# SCH_occitel_mini.net
KiCad netlist of a schematic drawn in EasyEDA
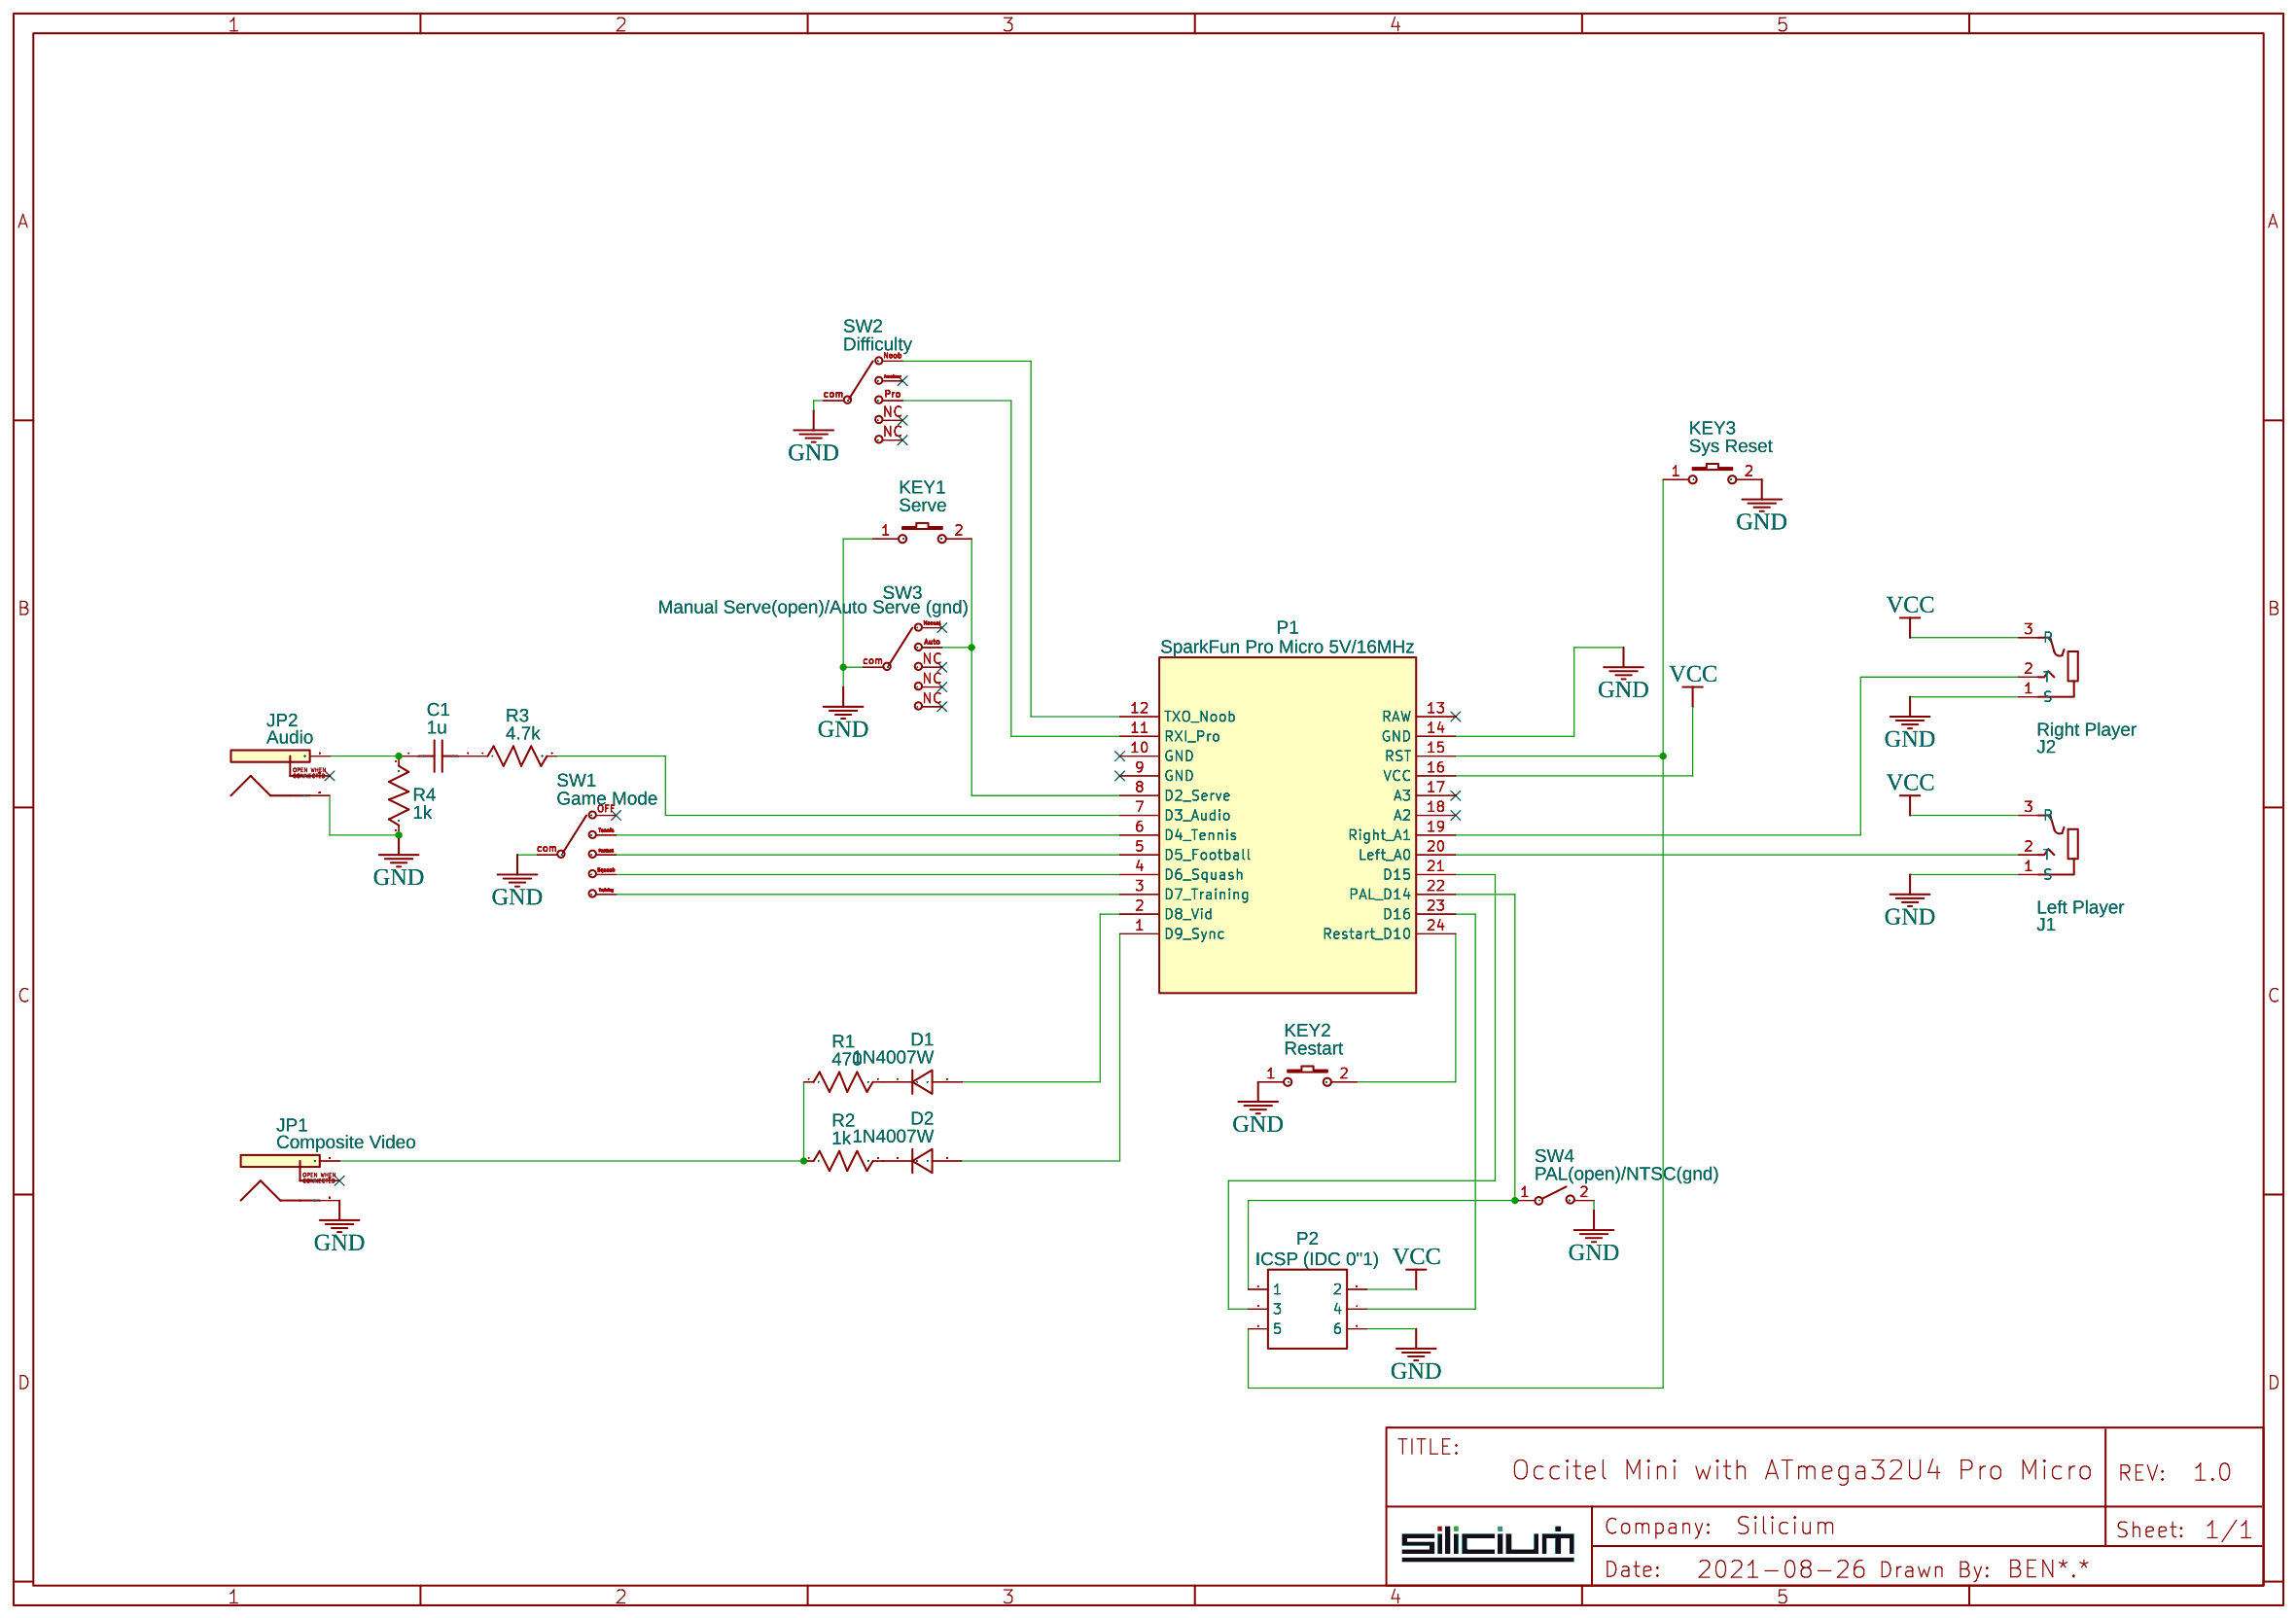
[diagram p0: schematic sheet]

(export (version "E")
  (design (tool "Eeschema 10.0.6"))
  (components
    (comp (ref "C1") (value "1u") (libsource (lib "") (part "C_0603_US")))
    (comp (ref "D1")
      (value "1N4007W")
      (fields (field (name "BOM_Supplier Part") "C328592"))
      (libsource (lib "") (part "1N4007W"))
    )
    (comp (ref "D2")
      (value "1N4007W")
      (fields (field (name "BOM_Supplier Part") "C328592"))
      (libsource (lib "") (part "1N4007W"))
    )
    (comp (ref "J1") (value "Left Player") (libsource (lib "") (part "Jack_3.5mm_3pin")))
    (comp (ref "J2") (value "Right Player") (libsource (lib "") (part "Jack_3.5mm_3pin")))
    (comp (ref "JP1") (value "Composite Video") (libsource (lib "") (part "RCA-LOCK")))
    (comp (ref "JP2") (value "Audio") (libsource (lib "") (part "RCA-LOCK")))
    (comp (ref "KEY1")
      (value "Serve")
      (fields
        (field (name "BOM_Manufacturer Part") "K2-1107ST-A4SW-06")
        (field (name "BOM_Supplier Part") "C118141")
      )
      (libsource (lib "") (part "K2-3.6×6.1_SMD"))
    )
    (comp (ref "KEY2")
      (value "Restart")
      (fields
        (field (name "BOM_Manufacturer Part") "K2-1107ST-A4SW-06")
        (field (name "BOM_Supplier Part") "C118141")
      )
      (libsource (lib "") (part "K2-3.6×6.1_SMD"))
    )
    (comp (ref "KEY3")
      (value "Sys Reset")
      (fields
        (field (name "BOM_Manufacturer Part") "K2-1107ST-A4SW-06")
        (field (name "BOM_Supplier Part") "C118141")
      )
      (libsource (lib "") (part "K2-3.6×6.1_SMD"))
    )
    (comp (ref "P1") (value "SparkFun Pro Micro 5V/16MHz") (libsource (lib "") (part "Pro Micro - 5V")))
    (comp (ref "P2")
      (value "ICSP (IDC 0\"1)")
      (fields
        (field (name "BOM_Manufacturer Part") "2X3 2.54mm IDC Box")
        (field (name "BOM_Supplier Part") "C11214")
      )
      (libsource (lib "") (part "HDR-IDC-2.54-2X3P"))
    )
    (comp (ref "R1") (value "470") (libsource (lib "") (part "R_0603_US")))
    (comp (ref "R2") (value "1k") (libsource (lib "") (part "R_0603_US")))
    (comp (ref "R3") (value "4.7k") (libsource (lib "") (part "R_0603_US")))
    (comp (ref "R4") (value "1k") (libsource (lib "") (part "R_0603_US_1")))
    (comp (ref "SW1") (value "Game Mode") (libsource (lib "") (part "SW_SP5T_2")))
    (comp (ref "SW2") (value "Difficulty") (libsource (lib "") (part "SW_SP5T_1")))
    (comp (ref "SW3") (value "Manual Serve(open)/Auto Serve (gnd)") (libsource (lib "") (part "SW_SP5T")))
    (comp (ref "SW4") (value "PAL(open)/NTSC(gnd)") (libsource (lib "") (part "SW_SPST")))
  )
  (nets
    (net (code "1") (name "GND") (class "Default")
      (node (ref "J1") (pin "1") (pinfunction "S_1") (pintype "unspecified"))
      (node (ref "J2") (pin "1") (pinfunction "S_1") (pintype "unspecified"))
      (node (ref "JP1") (pin "SHELL") (pinfunction "SHELL_SHELL") (pintype "unspecified"))
      (node (ref "JP2") (pin "SHELL") (pinfunction "SHELL_SHELL") (pintype "unspecified"))
      (node (ref "KEY1") (pin "1") (pinfunction "1_1") (pintype "unspecified"))
      (node (ref "KEY2") (pin "1") (pinfunction "1_1") (pintype "unspecified"))
      (node (ref "KEY3") (pin "2") (pinfunction "2_2") (pintype "unspecified"))
      (node (ref "P1") (pin "14") (pinfunction "GND_14") (pintype "unspecified"))
      (node (ref "P2") (pin "6") (pinfunction "6_6") (pintype "unspecified"))
      (node (ref "R4") (pin "1") (pinfunction "1_1") (pintype "unspecified"))
      (node (ref "SW1") (pin "com") (pinfunction "3_com") (pintype "unspecified"))
      (node (ref "SW2") (pin "com") (pinfunction "3_com") (pintype "unspecified"))
      (node (ref "SW3") (pin "com") (pinfunction "3_com") (pintype "unspecified"))
      (node (ref "SW4") (pin "2") (pinfunction "B_2") (pintype "input"))
    )
    (net (code "2") (name "Net-(C1-Pad1)") (class "Default")
      (node (ref "C1") (pin "1") (pinfunction "1_1") (pintype "unspecified"))
      (node (ref "JP2") (pin "PIN") (pinfunction "PIN_PIN") (pintype "unspecified"))
      (node (ref "R4") (pin "2") (pinfunction "2_2") (pintype "unspecified"))
    )
    (net (code "3") (name "Net-(C1-Pad2)") (class "Default")
      (node (ref "C1") (pin "2") (pinfunction "2_2") (pintype "unspecified"))
      (node (ref "R3") (pin "1") (pinfunction "1_1") (pintype "unspecified"))
    )
    (net (code "4") (name "Net-(D1-Pad1)") (class "Default")
      (node (ref "D1") (pin "1") (pinfunction "1_1") (pintype "unspecified"))
      (node (ref "R1") (pin "2") (pinfunction "2_2") (pintype "unspecified"))
    )
    (net (code "5") (name "Net-(D2-Pad1)") (class "Default")
      (node (ref "D2") (pin "1") (pinfunction "1_1") (pintype "unspecified"))
      (node (ref "R2") (pin "2") (pinfunction "2_2") (pintype "unspecified"))
    )
    (net (code "6") (name "Net-(J1-T)") (class "Default")
      (node (ref "J1") (pin "2") (pinfunction "T_2") (pintype "unspecified"))
      (node (ref "P1") (pin "20") (pinfunction "Left_A0_20") (pintype "unspecified"))
    )
    (net (code "7") (name "Net-(J2-T)") (class "Default")
      (node (ref "J2") (pin "2") (pinfunction "T_2") (pintype "unspecified"))
      (node (ref "P1") (pin "19") (pinfunction "Right_A1_19") (pintype "unspecified"))
    )
    (net (code "8") (name "Net-(JP1-PadPIN)") (class "Default")
      (node (ref "JP1") (pin "PIN") (pinfunction "PIN_PIN") (pintype "unspecified"))
      (node (ref "R1") (pin "1") (pinfunction "1_1") (pintype "unspecified"))
      (node (ref "R2") (pin "1") (pinfunction "1_1") (pintype "unspecified"))
    )
    (net (code "9") (name "Net-(P1-D2_Serve)") (class "Default")
      (node (ref "KEY1") (pin "2") (pinfunction "2_2") (pintype "unspecified"))
      (node (ref "P1") (pin "8") (pinfunction "D2_Serve_8") (pintype "unspecified"))
      (node (ref "SW3") (pin "Auto") (pinfunction "2_Auto") (pintype "unspecified"))
    )
    (net (code "10") (name "Net-(P1-D3_Audio)") (class "Default")
      (node (ref "P1") (pin "7") (pinfunction "D3_Audio_7") (pintype "unspecified"))
      (node (ref "R3") (pin "2") (pinfunction "2_2") (pintype "unspecified"))
    )
    (net (code "11") (name "Net-(P1-D4_Tennis)") (class "Default")
      (node (ref "P1") (pin "6") (pinfunction "D4_Tennis_6") (pintype "unspecified"))
      (node (ref "SW1") (pin "Tennis") (pinfunction "2_Tennis") (pintype "unspecified"))
    )
    (net (code "12") (name "Net-(P1-D5_Football)") (class "Default")
      (node (ref "P1") (pin "5") (pinfunction "D5_Football_5") (pintype "unspecified"))
      (node (ref "SW1") (pin "Football") (pinfunction "4_Football") (pintype "unspecified"))
    )
    (net (code "13") (name "Net-(P1-D6_Squash)") (class "Default")
      (node (ref "P1") (pin "4") (pinfunction "D6_Squash_4") (pintype "unspecified"))
      (node (ref "SW1") (pin "Squash") (pinfunction "4_Squash") (pintype "unspecified"))
    )
    (net (code "14") (name "Net-(P1-D7_Training)") (class "Default")
      (node (ref "P1") (pin "3") (pinfunction "D7_Training_3") (pintype "unspecified"))
      (node (ref "SW1") (pin "Training") (pinfunction "4_Training") (pintype "unspecified"))
    )
    (net (code "15") (name "Net-(P1-D8_Vid)") (class "Default")
      (node (ref "D1") (pin "2") (pinfunction "2_2") (pintype "unspecified"))
      (node (ref "P1") (pin "2") (pinfunction "D8_Vid_2") (pintype "unspecified"))
    )
    (net (code "16") (name "Net-(P1-D9_Sync)") (class "Default")
      (node (ref "D2") (pin "2") (pinfunction "2_2") (pintype "unspecified"))
      (node (ref "P1") (pin "1") (pinfunction "D9_Sync_1") (pintype "unspecified"))
    )
    (net (code "17") (name "Net-(P1-D15)") (class "Default")
      (node (ref "P1") (pin "21") (pinfunction "D15_21") (pintype "unspecified"))
      (node (ref "P2") (pin "3") (pinfunction "3_3") (pintype "unspecified"))
    )
    (net (code "18") (name "Net-(P1-D16)") (class "Default")
      (node (ref "P1") (pin "23") (pinfunction "D16_23") (pintype "unspecified"))
      (node (ref "P2") (pin "4") (pinfunction "4_4") (pintype "unspecified"))
    )
    (net (code "19") (name "Net-(P1-PAL_D14)") (class "Default")
      (node (ref "P1") (pin "22") (pinfunction "PAL_D14_22") (pintype "unspecified"))
      (node (ref "P2") (pin "1") (pinfunction "1_1") (pintype "unspecified"))
      (node (ref "SW4") (pin "1") (pinfunction "A_1") (pintype "input"))
    )
    (net (code "20") (name "Net-(P1-RST)") (class "Default")
      (node (ref "KEY3") (pin "1") (pinfunction "1_1") (pintype "unspecified"))
      (node (ref "P1") (pin "15") (pinfunction "RST_15") (pintype "unspecified"))
      (node (ref "P2") (pin "5") (pinfunction "5_5") (pintype "unspecified"))
    )
    (net (code "21") (name "Net-(P1-RXI_Pro)") (class "Default")
      (node (ref "P1") (pin "11") (pinfunction "RXI_Pro_11") (pintype "unspecified"))
      (node (ref "SW2") (pin "Pro") (pinfunction "4_Pro") (pintype "unspecified"))
    )
    (net (code "22") (name "Net-(P1-Restart_D10)") (class "Default")
      (node (ref "KEY2") (pin "2") (pinfunction "2_2") (pintype "unspecified"))
      (node (ref "P1") (pin "24") (pinfunction "Restart_D10_24") (pintype "unspecified"))
    )
    (net (code "23") (name "Net-(P1-TXO_Noob)") (class "Default")
      (node (ref "P1") (pin "12") (pinfunction "TXO_Noob_12") (pintype "unspecified"))
      (node (ref "SW2") (pin "Noob") (pinfunction "1_Noob") (pintype "unspecified"))
    )
    (net (code "24") (name "VCC") (class "Default")
      (node (ref "J1") (pin "3") (pinfunction "R_3") (pintype "unspecified"))
      (node (ref "J2") (pin "3") (pinfunction "R_3") (pintype "unspecified"))
      (node (ref "P1") (pin "16") (pinfunction "VCC_16") (pintype "unspecified"))
      (node (ref "P2") (pin "2") (pinfunction "2_2") (pintype "unspecified"))
    )
    (net (code "25") (name "unconnected-(JP1-PadSWITCH)") (class "Default")
      (node (ref "JP1") (pin "SWITCH") (pinfunction "SWITCH_SWITCH") (pintype "unspecified+no_connect"))
    )
    (net (code "26") (name "unconnected-(JP2-PadSWITCH)") (class "Default")
      (node (ref "JP2") (pin "SWITCH") (pinfunction "SWITCH_SWITCH") (pintype "unspecified+no_connect"))
    )
    (net (code "27") (name "unconnected-(P1-A2-Pad18)") (class "Default")
      (node (ref "P1") (pin "18") (pinfunction "A2_18") (pintype "unspecified+no_connect"))
    )
    (net (code "28") (name "unconnected-(P1-A3-Pad17)") (class "Default")
      (node (ref "P1") (pin "17") (pinfunction "A3_17") (pintype "unspecified+no_connect"))
    )
    (net (code "29") (name "unconnected-(P1-GND-Pad9)") (class "Default")
      (node (ref "P1") (pin "9") (pinfunction "GND_9") (pintype "unspecified+no_connect"))
    )
    (net (code "30") (name "unconnected-(P1-GND-Pad10)") (class "Default")
      (node (ref "P1") (pin "10") (pinfunction "GND_10") (pintype "unspecified+no_connect"))
    )
    (net (code "31") (name "unconnected-(P1-RAW-Pad13)") (class "Default")
      (node (ref "P1") (pin "13") (pinfunction "RAW_13") (pintype "unspecified+no_connect"))
    )
    (net (code "32") (name "unconnected-(SW1-1-PadOFF)") (class "Default")
      (node (ref "SW1") (pin "OFF") (pinfunction "1_OFF") (pintype "unspecified+no_connect"))
    )
    (net (code "33") (name "unconnected-(SW2-2-PadAmateur)") (class "Default")
      (node (ref "SW2") (pin "Amateur") (pinfunction "2_Amateur") (pintype "unspecified+no_connect"))
    )
    (net (code "34") (name "unconnected-(SW2-4-PadNC)") (class "Default")
      (node (ref "SW2") (pin "NC") (pinfunction "4_NC") (pintype "unspecified+no_connect"))
    )
    (net (code "35") (name "unconnected-(SW2-4-PadNC)_1") (class "Default")
      (node (ref "SW2") (pin "NC") (pinfunction "4_NC") (pintype "unspecified+no_connect"))
    )
    (net (code "36") (name "unconnected-(SW3-1-PadManual)") (class "Default")
      (node (ref "SW3") (pin "Manual") (pinfunction "1_Manual") (pintype "unspecified+no_connect"))
    )
    (net (code "37") (name "unconnected-(SW3-4-PadNC)") (class "Default")
      (node (ref "SW3") (pin "NC") (pinfunction "4_NC") (pintype "unspecified+no_connect"))
    )
    (net (code "38") (name "unconnected-(SW3-4-PadNC)_1") (class "Default")
      (node (ref "SW3") (pin "NC") (pinfunction "4_NC") (pintype "unspecified+no_connect"))
    )
    (net (code "39") (name "unconnected-(SW3-4-PadNC)_2") (class "Default")
      (node (ref "SW3") (pin "NC") (pinfunction "4_NC") (pintype "unspecified+no_connect"))
    )
  )
)
